# Rover_Motor_Controller_R2.net
KiCad netlist of a schematic drawn in EAGLE
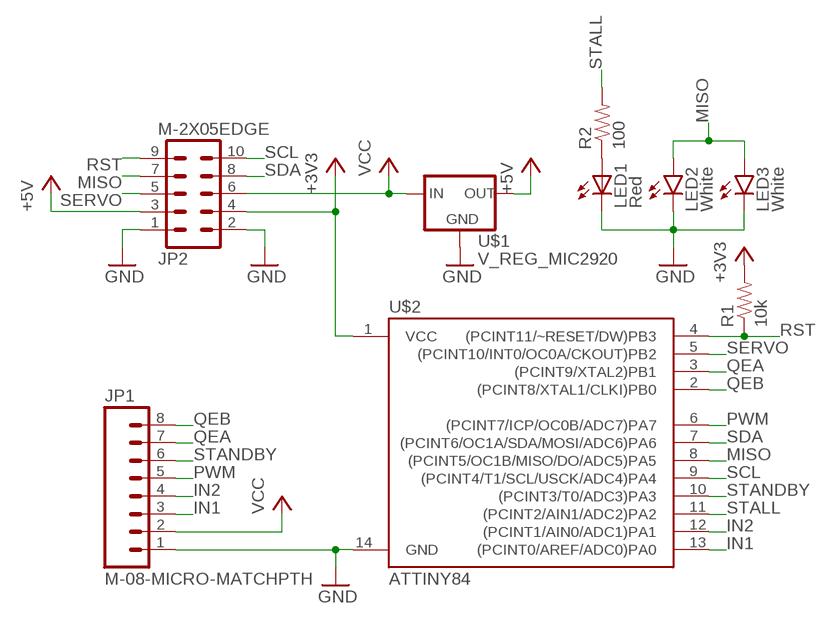
[diagram p0: schematic, sheet 1]

(export (version "E")
  (design (tool "Eeschema 10.0.6"))
  (components
    (comp (ref "JP1")
      (value "M-08-MICRO-MATCHPTH")
      (footprint "eagle-import:M-08-MICRO-MATCH-PTH")
      (libsource (lib "eagle-import") (part "M-08-MICRO-MATCHPTH"))
    )
    (comp (ref "JP2")
      (value "M-2X05EDGE")
      (footprint "eagle-import:M-2X05-0.1-EDGE")
      (libsource (lib "eagle-import") (part "M-2X05EDGE"))
    )
    (comp (ref "LED1")
      (value "Red")
      (footprint "eagle-import:SML0603")
      (libsource (lib "eagle-import") (part "LEDSML0603"))
    )
    (comp (ref "LED2")
      (value "White")
      (footprint "eagle-import:LED-SMD-RA")
      (libsource (lib "eagle-import") (part "LEDSMD-RA"))
    )
    (comp (ref "LED3")
      (value "White")
      (footprint "eagle-import:LED-SMD-RA")
      (libsource (lib "eagle-import") (part "LEDSMD-RA"))
    )
    (comp (ref "R1")
      (value "10k")
      (footprint "eagle-import:R0603")
      (libsource (lib "eagle-import") (part "RESISTOR0603"))
    )
    (comp (ref "R2")
      (value "100")
      (footprint "eagle-import:R0603")
      (libsource (lib "eagle-import") (part "RESISTOR0603"))
    )
    (comp (ref "U$1")
      (value "V_REG_MIC2920")
      (footprint "eagle-import:SOT223")
      (libsource (lib "eagle-import") (part "V_REG_MIC2920"))
    )
    (comp (ref "U$2")
      (value "ATTINY84")
      (footprint "eagle-import:SO14")
      (libsource (lib "eagle-import") (part "ATTINY84"))
    )
  )
  (nets
    (net (code "1") (name "+3V3") (class "Default")
      (node (ref "JP2") (pin "4") (pinfunction "4_4") (pintype "passive"))
      (node (ref "R1") (pin "2") (pinfunction "2_2") (pintype "passive"))
      (node (ref "U$2") (pin "1") (pinfunction "VCC_1") (pintype "bidirectional"))
    )
    (net (code "2") (name "+5V") (class "Default")
      (node (ref "JP2") (pin "3") (pinfunction "3_3") (pintype "passive"))
      (node (ref "U$1") (pin "3") (pinfunction "OUT_3") (pintype "output"))
    )
    (net (code "3") (name "/IN1") (class "Default")
      (node (ref "JP1") (pin "3") (pinfunction "3_3") (pintype "passive"))
      (node (ref "U$2") (pin "13") (pinfunction "(PCINT0/AREF/ADC0)PA0_13") (pintype "bidirectional"))
    )
    (net (code "4") (name "/IN2") (class "Default")
      (node (ref "JP1") (pin "4") (pinfunction "4_4") (pintype "passive"))
      (node (ref "U$2") (pin "12") (pinfunction "(PCINT1/AIN0/ADC1)PA1_12") (pintype "bidirectional"))
    )
    (net (code "5") (name "/MISO") (class "Default")
      (node (ref "JP2") (pin "7") (pinfunction "7_7") (pintype "passive"))
      (node (ref "LED2") (pin "A") (pinfunction "A_A") (pintype "passive"))
      (node (ref "LED3") (pin "A") (pinfunction "A_A") (pintype "passive"))
      (node (ref "U$2") (pin "8") (pinfunction "(PCINT5/OC1B/MISO/DO/ADC5)PA5_8") (pintype "bidirectional"))
    )
    (net (code "6") (name "/PWM") (class "Default")
      (node (ref "JP1") (pin "5") (pinfunction "5_5") (pintype "passive"))
      (node (ref "U$2") (pin "6") (pinfunction "(PCINT7/ICP/OC0B/ADC7)PA7_6") (pintype "bidirectional"))
    )
    (net (code "7") (name "/QEA") (class "Default")
      (node (ref "JP1") (pin "7") (pinfunction "7_7") (pintype "passive"))
      (node (ref "U$2") (pin "3") (pinfunction "(PCINT9/XTAL2)PB1_3") (pintype "bidirectional"))
    )
    (net (code "8") (name "/QEB") (class "Default")
      (node (ref "JP1") (pin "8") (pinfunction "8_8") (pintype "passive"))
      (node (ref "U$2") (pin "2") (pinfunction "(PCINT8/XTAL1/CLKI)PB0_2") (pintype "bidirectional"))
    )
    (net (code "9") (name "/RST") (class "Default")
      (node (ref "JP2") (pin "9") (pinfunction "9_9") (pintype "passive"))
      (node (ref "R1") (pin "1") (pinfunction "1_1") (pintype "passive"))
      (node (ref "U$2") (pin "4") (pinfunction "(PCINT11/~{RESET/DW})PB3_4") (pintype "bidirectional"))
    )
    (net (code "10") (name "/SCL") (class "Default")
      (node (ref "JP2") (pin "10") (pinfunction "10_10") (pintype "passive"))
      (node (ref "U$2") (pin "9") (pinfunction "(PCINT4/T1/SCL/USCK/ADC4)PA4_9") (pintype "bidirectional"))
    )
    (net (code "11") (name "/SDA") (class "Default")
      (node (ref "JP2") (pin "8") (pinfunction "8_8") (pintype "passive"))
      (node (ref "U$2") (pin "7") (pinfunction "(PCINT6/OC1A/SDA/MOSI/ADC6)PA6_7") (pintype "bidirectional"))
    )
    (net (code "12") (name "/SERVO") (class "Default")
      (node (ref "JP2") (pin "5") (pinfunction "5_5") (pintype "passive"))
      (node (ref "U$2") (pin "5") (pinfunction "(PCINT10/INT0/OC0A/CKOUT)PB2_5") (pintype "bidirectional"))
    )
    (net (code "13") (name "/STALL") (class "Default")
      (node (ref "R2") (pin "2") (pinfunction "2_2") (pintype "passive"))
      (node (ref "U$2") (pin "11") (pinfunction "(PCINT2/AIN1/ADC2)PA2_11") (pintype "bidirectional"))
    )
    (net (code "14") (name "/STANDBY") (class "Default")
      (node (ref "JP1") (pin "6") (pinfunction "6_6") (pintype "passive"))
      (node (ref "U$2") (pin "10") (pinfunction "(PCINT3/T0/ADC3)PA3_10") (pintype "bidirectional"))
    )
    (net (code "15") (name "GND") (class "Default")
      (node (ref "JP1") (pin "1") (pinfunction "1_1") (pintype "passive"))
      (node (ref "JP2") (pin "1") (pinfunction "1_1") (pintype "passive"))
      (node (ref "JP2") (pin "2") (pinfunction "2_2") (pintype "passive"))
      (node (ref "LED1") (pin "C") (pinfunction "C_C") (pintype "passive"))
      (node (ref "LED2") (pin "C") (pinfunction "C_C") (pintype "passive"))
      (node (ref "LED3") (pin "C") (pinfunction "C_C") (pintype "passive"))
      (node (ref "U$1") (pin "2") (pinfunction "GND_2") (pintype "input"))
      (node (ref "U$2") (pin "14") (pinfunction "GND_14") (pintype "bidirectional"))
    )
    (net (code "16") (name "Net-(LED1-PadA)") (class "Default")
      (node (ref "LED1") (pin "A") (pinfunction "A_A") (pintype "passive"))
      (node (ref "R2") (pin "1") (pinfunction "1_1") (pintype "passive"))
    )
    (net (code "17") (name "VCC") (class "Default")
      (node (ref "JP1") (pin "2") (pinfunction "2_2") (pintype "passive"))
      (node (ref "JP2") (pin "6") (pinfunction "6_6") (pintype "passive"))
      (node (ref "U$1") (pin "1") (pinfunction "IN_1") (pintype "input"))
    )
  )
)
